# SWD_Breakout.net
KiCad netlist of a schematic drawn in Altium Designer
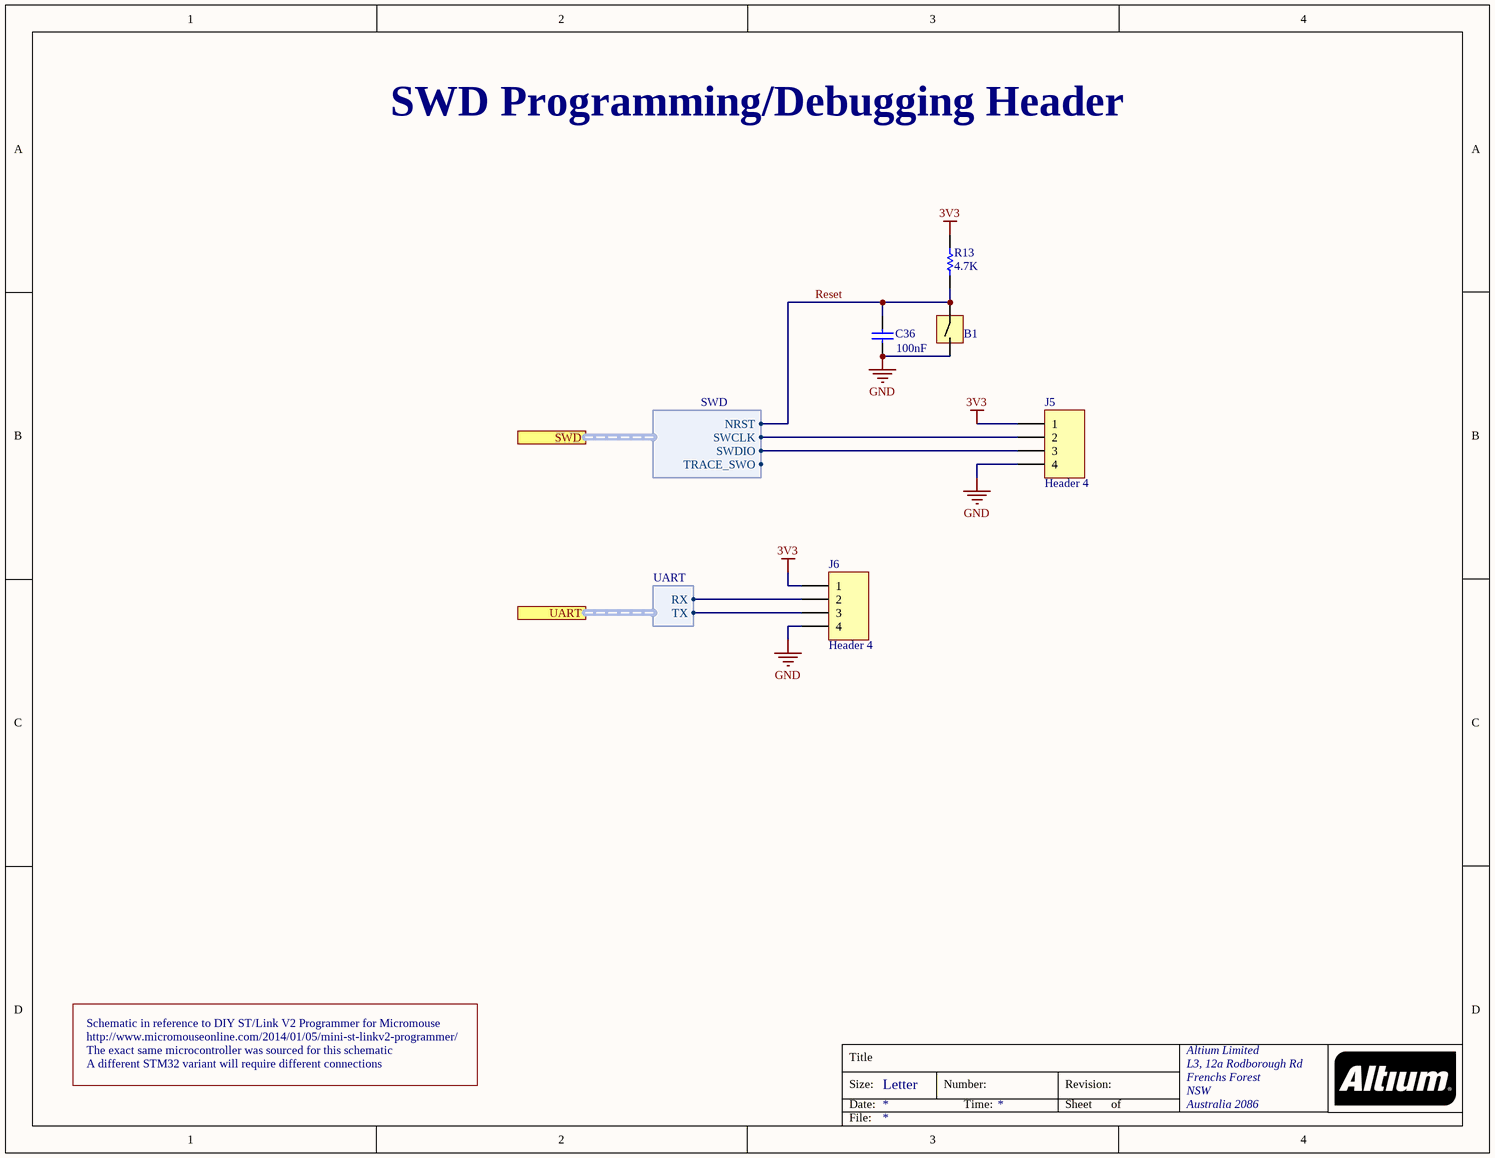
[diagram p0: SWD_Breakout.SchDoc]

(export (version "E")
  (design (tool "Eeschema 10.0.6"))
  (components
    (comp (ref "B1")
      (value "Push Button")
      (footprint "PUSHBUTTON")
      (libsource (lib "LaunchyRIOComponents") (part "PushButton"))
    )
    (comp (ref "C36")
      (value "100nF")
      (footprint "CAP_0603")
      (description "Capacitor")
      (fields (field (name "Comment") "Cap"))
      (libsource (lib "Miscellaneous Devices") (part "Cap"))
    )
    (comp (ref "J5")
      (value "Header 4")
      (footprint "HDR1X4")
      (description "Header, 4-Pin")
      (fields (field (name "PUBLISHER") "Altium Limited"))
      (libsource (lib "Miscellaneous Connectors") (part "Header 4"))
    )
    (comp (ref "J6")
      (value "Header 4")
      (footprint "HDR1X4")
      (description "Header, 4-Pin")
      (fields (field (name "PUBLISHER") "Altium Limited"))
      (libsource (lib "Miscellaneous Connectors") (part "Header 4"))
    )
    (comp (ref "R13")
      (value "4.7K")
      (footprint "RES_0603")
      (description "Resistor")
      (fields (field (name "Comment") "Res1"))
      (libsource (lib "Miscellaneous Devices") (part "Res1"))
    )
  )
  (nets
    (net (code "3") (name "/RX") (class "Default")
      (node (ref "J6") (pin "2") (pinfunction "2_2") (pintype "passive"))
    )
    (net (code "4") (name "/Reset") (class "Default")
      (node (ref "B1") (pin "1") (pinfunction "0_1") (pintype "passive"))
      (node (ref "C36") (pin "2") (pinfunction "2_2") (pintype "passive"))
      (node (ref "R13") (pin "1") (pinfunction "1_1") (pintype "passive"))
    )
    (net (code "5") (name "/SWCLK") (class "Default")
      (node (ref "J5") (pin "2") (pinfunction "2_2") (pintype "passive"))
    )
    (net (code "6") (name "/SWDIO") (class "Default")
      (node (ref "J5") (pin "3") (pinfunction "3_3") (pintype "passive"))
    )
    (net (code "7") (name "/TX") (class "Default")
      (node (ref "J6") (pin "3") (pinfunction "3_3") (pintype "passive"))
    )
    (net (code "10") (name "3V3") (class "Default")
      (node (ref "J5") (pin "1") (pinfunction "1_1") (pintype "passive"))
      (node (ref "J6") (pin "1") (pinfunction "1_1") (pintype "passive"))
      (node (ref "R13") (pin "2") (pinfunction "2_2") (pintype "passive"))
    )
    (net (code "11") (name "GND") (class "Default")
      (node (ref "B1") (pin "2") (pinfunction "1_2") (pintype "passive"))
      (node (ref "C36") (pin "1") (pinfunction "1_1") (pintype "passive"))
      (node (ref "J5") (pin "4") (pinfunction "4_4") (pintype "passive"))
      (node (ref "J6") (pin "4") (pinfunction "4_4") (pintype "passive"))
    )
  )
)
